# SN74LVC4245A.net
KiCad netlist of a schematic drawn in Altium Designer
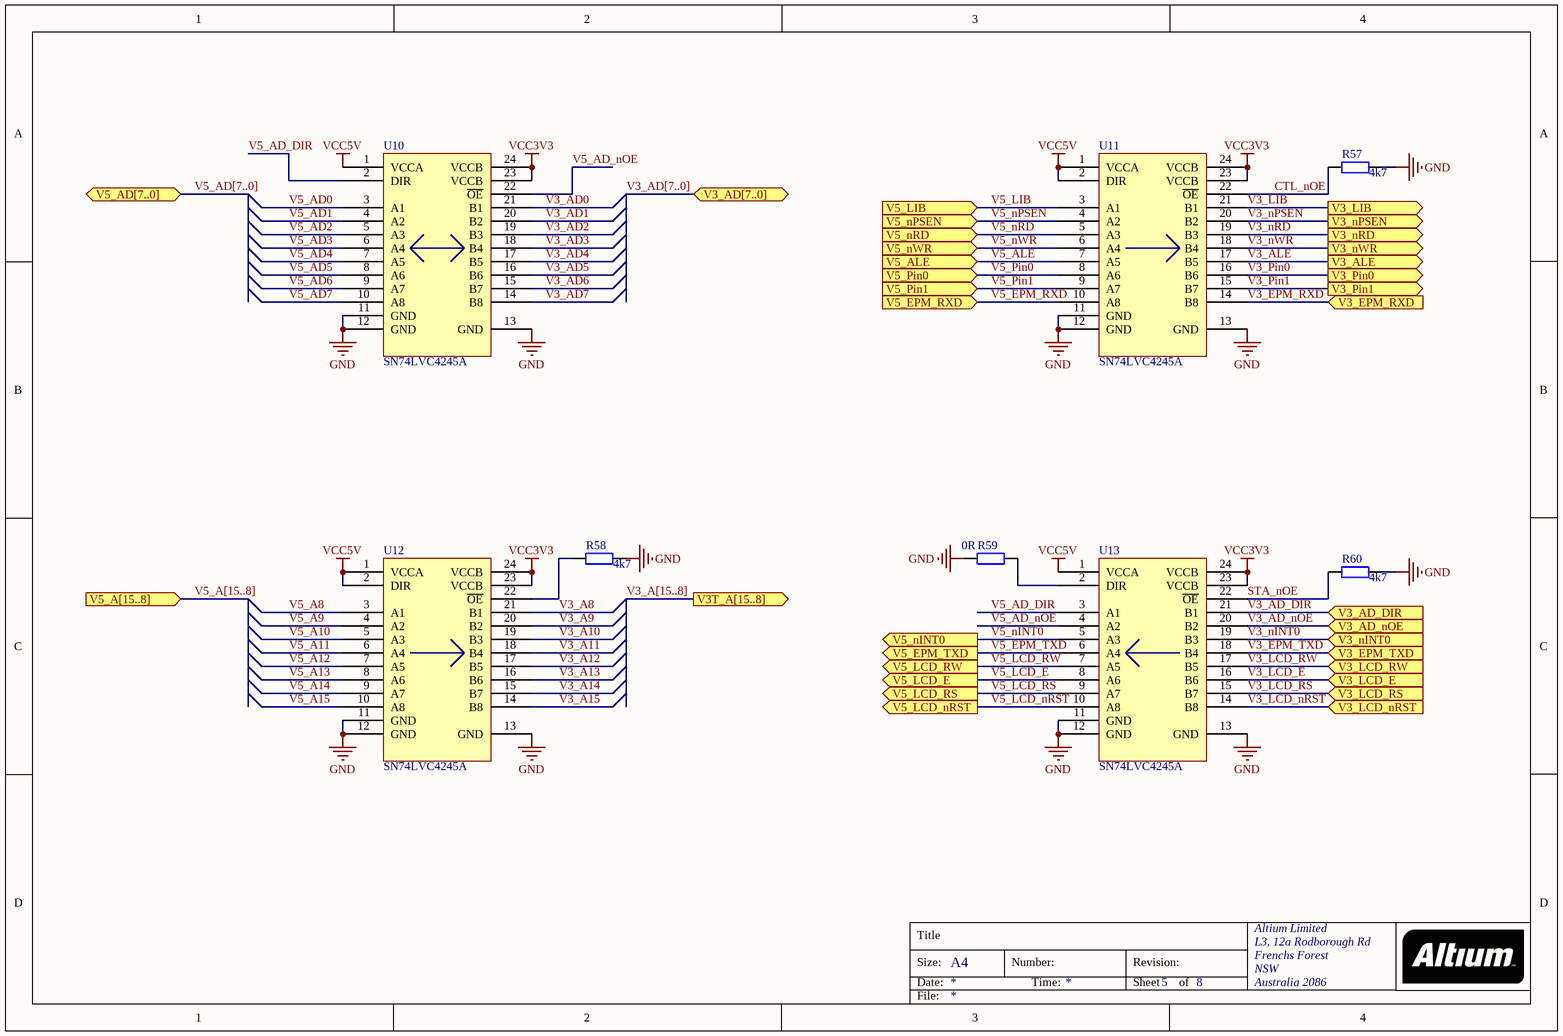
[diagram p0: SN74LVC4245A.SchDoc]

(export (version "E")
  (design (tool "Eeschema 10.0.6"))
  (components
    (comp (ref "R57") (value "4k7") (footprint "R0603") (libsource (lib "MyYX") (part "RES_04")))
    (comp (ref "R58") (value "4k7") (footprint "R0603") (libsource (lib "MyYX") (part "RES_04")))
    (comp (ref "R59") (value "0R") (footprint "R0603") (libsource (lib "MyYX") (part "RES_04")))
    (comp (ref "R60") (value "4k7") (footprint "R0603") (libsource (lib "MyYX") (part "RES_04")))
    (comp (ref "U10")
      (value "SN74LVC4245A")
      (footprint "TSSOP-24")
      (libsource (lib "MyYX") (part "SN74LVC4245A-SOIC"))
    )
    (comp (ref "U11")
      (value "SN74LVC4245A")
      (footprint "TSSOP-24")
      (libsource (lib "MyYX") (part "SN74LVC4245A-SOIC"))
    )
    (comp (ref "U12")
      (value "SN74LVC4245A")
      (footprint "TSSOP-24")
      (libsource (lib "MyYX") (part "SN74LVC4245A-SOIC"))
    )
    (comp (ref "U13")
      (value "SN74LVC4245A")
      (footprint "TSSOP-24")
      (libsource (lib "MyYX") (part "SN74LVC4245A-SOIC"))
    )
  )
  (nets
    (net (code "1") (name "/CTL_nOE") (class "Default")
      (node (ref "R57") (pin "2") (pinfunction "2_2") (pintype "passive"))
      (node (ref "U11") (pin "22") (pinfunction "~{OE}_22") (pintype "passive"))
    )
    (net (code "2") (name "/STA_nOE") (class "Default")
      (node (ref "R60") (pin "2") (pinfunction "2_2") (pintype "passive"))
      (node (ref "U13") (pin "22") (pinfunction "~{OE}_22") (pintype "passive"))
    )
    (net (code "3") (name "/V3_A8") (class "Default")
      (node (ref "U12") (pin "21") (pinfunction "B1_21") (pintype "passive"))
    )
    (net (code "4") (name "/V3_A9") (class "Default")
      (node (ref "U12") (pin "20") (pinfunction "B2_20") (pintype "passive"))
    )
    (net (code "5") (name "/V3_A10") (class "Default")
      (node (ref "U12") (pin "19") (pinfunction "B3_19") (pintype "passive"))
    )
    (net (code "6") (name "/V3_A11") (class "Default")
      (node (ref "U12") (pin "18") (pinfunction "B4_18") (pintype "passive"))
    )
    (net (code "7") (name "/V3_A12") (class "Default")
      (node (ref "U12") (pin "17") (pinfunction "B5_17") (pintype "passive"))
    )
    (net (code "8") (name "/V3_A13") (class "Default")
      (node (ref "U12") (pin "16") (pinfunction "B6_16") (pintype "passive"))
    )
    (net (code "9") (name "/V3_A14") (class "Default")
      (node (ref "U12") (pin "15") (pinfunction "B7_15") (pintype "passive"))
    )
    (net (code "10") (name "/V3_A15") (class "Default")
      (node (ref "U12") (pin "14") (pinfunction "B8_14") (pintype "passive"))
    )
    (net (code "11") (name "/V3_AD0") (class "Default")
      (node (ref "U10") (pin "21") (pinfunction "B1_21") (pintype "passive"))
    )
    (net (code "12") (name "/V3_AD1") (class "Default")
      (node (ref "U10") (pin "20") (pinfunction "B2_20") (pintype "passive"))
    )
    (net (code "13") (name "/V3_AD2") (class "Default")
      (node (ref "U10") (pin "19") (pinfunction "B3_19") (pintype "passive"))
    )
    (net (code "14") (name "/V3_AD3") (class "Default")
      (node (ref "U10") (pin "18") (pinfunction "B4_18") (pintype "passive"))
    )
    (net (code "15") (name "/V3_AD4") (class "Default")
      (node (ref "U10") (pin "17") (pinfunction "B5_17") (pintype "passive"))
    )
    (net (code "16") (name "/V3_AD5") (class "Default")
      (node (ref "U10") (pin "16") (pinfunction "B6_16") (pintype "passive"))
    )
    (net (code "17") (name "/V3_AD6") (class "Default")
      (node (ref "U10") (pin "15") (pinfunction "B7_15") (pintype "passive"))
    )
    (net (code "18") (name "/V3_AD7") (class "Default")
      (node (ref "U10") (pin "14") (pinfunction "B8_14") (pintype "passive"))
    )
    (net (code "20") (name "/V3_AD_DIR") (class "Default")
      (node (ref "U13") (pin "21") (pinfunction "B1_21") (pintype "passive"))
    )
    (net (code "21") (name "/V3_AD_nOE") (class "Default")
      (node (ref "U13") (pin "20") (pinfunction "B2_20") (pintype "passive"))
    )
    (net (code "22") (name "/V3_ALE") (class "Default")
      (node (ref "U11") (pin "17") (pinfunction "B5_17") (pintype "passive"))
    )
    (net (code "24") (name "/V3_EPM_RXD") (class "Default")
      (node (ref "U11") (pin "14") (pinfunction "B8_14") (pintype "passive"))
    )
    (net (code "25") (name "/V3_EPM_TXD") (class "Default")
      (node (ref "U13") (pin "18") (pinfunction "B4_18") (pintype "passive"))
    )
    (net (code "26") (name "/V3_LCD_E") (class "Default")
      (node (ref "U13") (pin "16") (pinfunction "B6_16") (pintype "passive"))
    )
    (net (code "27") (name "/V3_LCD_RS") (class "Default")
      (node (ref "U13") (pin "15") (pinfunction "B7_15") (pintype "passive"))
    )
    (net (code "28") (name "/V3_LCD_RW") (class "Default")
      (node (ref "U13") (pin "17") (pinfunction "B5_17") (pintype "passive"))
    )
    (net (code "29") (name "/V3_LCD_nRST") (class "Default")
      (node (ref "U13") (pin "14") (pinfunction "B8_14") (pintype "passive"))
    )
    (net (code "30") (name "/V3_LIB") (class "Default")
      (node (ref "U11") (pin "21") (pinfunction "B1_21") (pintype "passive"))
    )
    (net (code "31") (name "/V3_Pin0") (class "Default")
      (node (ref "U11") (pin "16") (pinfunction "B6_16") (pintype "passive"))
    )
    (net (code "32") (name "/V3_Pin1") (class "Default")
      (node (ref "U11") (pin "15") (pinfunction "B7_15") (pintype "passive"))
    )
    (net (code "33") (name "/V3_nINT0") (class "Default")
      (node (ref "U13") (pin "19") (pinfunction "B3_19") (pintype "passive"))
    )
    (net (code "34") (name "/V3_nPSEN") (class "Default")
      (node (ref "U11") (pin "20") (pinfunction "B2_20") (pintype "passive"))
    )
    (net (code "35") (name "/V3_nRD") (class "Default")
      (node (ref "U11") (pin "19") (pinfunction "B3_19") (pintype "passive"))
    )
    (net (code "36") (name "/V3_nWR") (class "Default")
      (node (ref "U11") (pin "18") (pinfunction "B4_18") (pintype "passive"))
    )
    (net (code "37") (name "/V5_A8") (class "Default")
      (node (ref "U12") (pin "3") (pinfunction "A1_3") (pintype "passive"))
    )
    (net (code "38") (name "/V5_A9") (class "Default")
      (node (ref "U12") (pin "4") (pinfunction "A2_4") (pintype "passive"))
    )
    (net (code "39") (name "/V5_A10") (class "Default")
      (node (ref "U12") (pin "5") (pinfunction "A3_5") (pintype "passive"))
    )
    (net (code "40") (name "/V5_A11") (class "Default")
      (node (ref "U12") (pin "6") (pinfunction "A4_6") (pintype "passive"))
    )
    (net (code "41") (name "/V5_A12") (class "Default")
      (node (ref "U12") (pin "7") (pinfunction "A5_7") (pintype "passive"))
    )
    (net (code "42") (name "/V5_A13") (class "Default")
      (node (ref "U12") (pin "8") (pinfunction "A6_8") (pintype "passive"))
    )
    (net (code "43") (name "/V5_A14") (class "Default")
      (node (ref "U12") (pin "9") (pinfunction "A7_9") (pintype "passive"))
    )
    (net (code "44") (name "/V5_A15") (class "Default")
      (node (ref "U12") (pin "10") (pinfunction "A8_10") (pintype "passive"))
    )
    (net (code "45") (name "/V5_AD0") (class "Default")
      (node (ref "U10") (pin "3") (pinfunction "A1_3") (pintype "passive"))
    )
    (net (code "46") (name "/V5_AD1") (class "Default")
      (node (ref "U10") (pin "4") (pinfunction "A2_4") (pintype "passive"))
    )
    (net (code "47") (name "/V5_AD2") (class "Default")
      (node (ref "U10") (pin "5") (pinfunction "A3_5") (pintype "passive"))
    )
    (net (code "48") (name "/V5_AD3") (class "Default")
      (node (ref "U10") (pin "6") (pinfunction "A4_6") (pintype "passive"))
    )
    (net (code "49") (name "/V5_AD4") (class "Default")
      (node (ref "U10") (pin "7") (pinfunction "A5_7") (pintype "passive"))
    )
    (net (code "50") (name "/V5_AD5") (class "Default")
      (node (ref "U10") (pin "8") (pinfunction "A6_8") (pintype "passive"))
    )
    (net (code "51") (name "/V5_AD6") (class "Default")
      (node (ref "U10") (pin "9") (pinfunction "A7_9") (pintype "passive"))
    )
    (net (code "52") (name "/V5_AD7") (class "Default")
      (node (ref "U10") (pin "10") (pinfunction "A8_10") (pintype "passive"))
    )
    (net (code "54") (name "/V5_AD_DIR") (class "Default")
      (node (ref "U10") (pin "2") (pinfunction "DIR_2") (pintype "passive"))
      (node (ref "U13") (pin "3") (pinfunction "A1_3") (pintype "passive"))
    )
    (net (code "55") (name "/V5_AD_nOE") (class "Default")
      (node (ref "U10") (pin "22") (pinfunction "~{OE}_22") (pintype "passive"))
      (node (ref "U13") (pin "4") (pinfunction "A2_4") (pintype "passive"))
    )
    (net (code "56") (name "/V5_ALE") (class "Default")
      (node (ref "U11") (pin "7") (pinfunction "A5_7") (pintype "passive"))
    )
    (net (code "58") (name "/V5_EPM_RXD") (class "Default")
      (node (ref "U11") (pin "10") (pinfunction "A8_10") (pintype "passive"))
    )
    (net (code "59") (name "/V5_EPM_TXD") (class "Default")
      (node (ref "U13") (pin "6") (pinfunction "A4_6") (pintype "passive"))
    )
    (net (code "60") (name "/V5_LCD_E") (class "Default")
      (node (ref "U13") (pin "8") (pinfunction "A6_8") (pintype "passive"))
    )
    (net (code "61") (name "/V5_LCD_RS") (class "Default")
      (node (ref "U13") (pin "9") (pinfunction "A7_9") (pintype "passive"))
    )
    (net (code "62") (name "/V5_LCD_RW") (class "Default")
      (node (ref "U13") (pin "7") (pinfunction "A5_7") (pintype "passive"))
    )
    (net (code "63") (name "/V5_LCD_nRST") (class "Default")
      (node (ref "U13") (pin "10") (pinfunction "A8_10") (pintype "passive"))
    )
    (net (code "64") (name "/V5_LIB") (class "Default")
      (node (ref "U11") (pin "3") (pinfunction "A1_3") (pintype "passive"))
    )
    (net (code "65") (name "/V5_Pin0") (class "Default")
      (node (ref "U11") (pin "8") (pinfunction "A6_8") (pintype "passive"))
    )
    (net (code "66") (name "/V5_Pin1") (class "Default")
      (node (ref "U11") (pin "9") (pinfunction "A7_9") (pintype "passive"))
    )
    (net (code "67") (name "/V5_nINT0") (class "Default")
      (node (ref "U13") (pin "5") (pinfunction "A3_5") (pintype "passive"))
    )
    (net (code "68") (name "/V5_nPSEN") (class "Default")
      (node (ref "U11") (pin "4") (pinfunction "A2_4") (pintype "passive"))
    )
    (net (code "69") (name "/V5_nRD") (class "Default")
      (node (ref "U11") (pin "5") (pinfunction "A3_5") (pintype "passive"))
    )
    (net (code "70") (name "/V5_nWR") (class "Default")
      (node (ref "U11") (pin "6") (pinfunction "A4_6") (pintype "passive"))
    )
    (net (code "71") (name "GND") (class "Default")
      (node (ref "R57") (pin "1") (pinfunction "1_1") (pintype "passive"))
      (node (ref "R58") (pin "1") (pinfunction "1_1") (pintype "passive"))
      (node (ref "R59") (pin "2") (pinfunction "2_2") (pintype "passive"))
      (node (ref "R60") (pin "1") (pinfunction "1_1") (pintype "passive"))
      (node (ref "U10") (pin "11") (pinfunction "GND_11") (pintype "passive"))
      (node (ref "U10") (pin "12") (pinfunction "GND_12") (pintype "passive"))
      (node (ref "U10") (pin "13") (pinfunction "GND_13") (pintype "passive"))
      (node (ref "U11") (pin "11") (pinfunction "GND_11") (pintype "passive"))
      (node (ref "U11") (pin "12") (pinfunction "GND_12") (pintype "passive"))
      (node (ref "U11") (pin "13") (pinfunction "GND_13") (pintype "passive"))
      (node (ref "U12") (pin "11") (pinfunction "GND_11") (pintype "passive"))
      (node (ref "U12") (pin "12") (pinfunction "GND_12") (pintype "passive"))
      (node (ref "U12") (pin "13") (pinfunction "GND_13") (pintype "passive"))
      (node (ref "U13") (pin "11") (pinfunction "GND_11") (pintype "passive"))
      (node (ref "U13") (pin "12") (pinfunction "GND_12") (pintype "passive"))
      (node (ref "U13") (pin "13") (pinfunction "GND_13") (pintype "passive"))
    )
    (net (code "72") (name "Net-(U12-~{OE})") (class "Default")
      (node (ref "R58") (pin "2") (pinfunction "2_2") (pintype "passive"))
      (node (ref "U12") (pin "22") (pinfunction "~{OE}_22") (pintype "passive"))
    )
    (net (code "73") (name "Net-(U13-DIR)") (class "Default")
      (node (ref "R59") (pin "1") (pinfunction "1_1") (pintype "passive"))
      (node (ref "U13") (pin "2") (pinfunction "DIR_2") (pintype "passive"))
    )
    (net (code "74") (name "VCC3V3") (class "Default")
      (node (ref "U10") (pin "23") (pinfunction "VCCB_23") (pintype "passive"))
      (node (ref "U10") (pin "24") (pinfunction "VCCB_24") (pintype "passive"))
      (node (ref "U11") (pin "23") (pinfunction "VCCB_23") (pintype "passive"))
      (node (ref "U11") (pin "24") (pinfunction "VCCB_24") (pintype "passive"))
      (node (ref "U12") (pin "23") (pinfunction "VCCB_23") (pintype "passive"))
      (node (ref "U12") (pin "24") (pinfunction "VCCB_24") (pintype "passive"))
      (node (ref "U13") (pin "23") (pinfunction "VCCB_23") (pintype "passive"))
      (node (ref "U13") (pin "24") (pinfunction "VCCB_24") (pintype "passive"))
    )
    (net (code "75") (name "VCC5V") (class "Default")
      (node (ref "U10") (pin "1") (pinfunction "VCCA_1") (pintype "passive"))
      (node (ref "U11") (pin "1") (pinfunction "VCCA_1") (pintype "passive"))
      (node (ref "U11") (pin "2") (pinfunction "DIR_2") (pintype "passive"))
      (node (ref "U12") (pin "1") (pinfunction "VCCA_1") (pintype "passive"))
      (node (ref "U12") (pin "2") (pinfunction "DIR_2") (pintype "passive"))
      (node (ref "U13") (pin "1") (pinfunction "VCCA_1") (pintype "passive"))
    )
  )
)
